# Main.net
KiCad netlist of a schematic drawn in Altium Designer
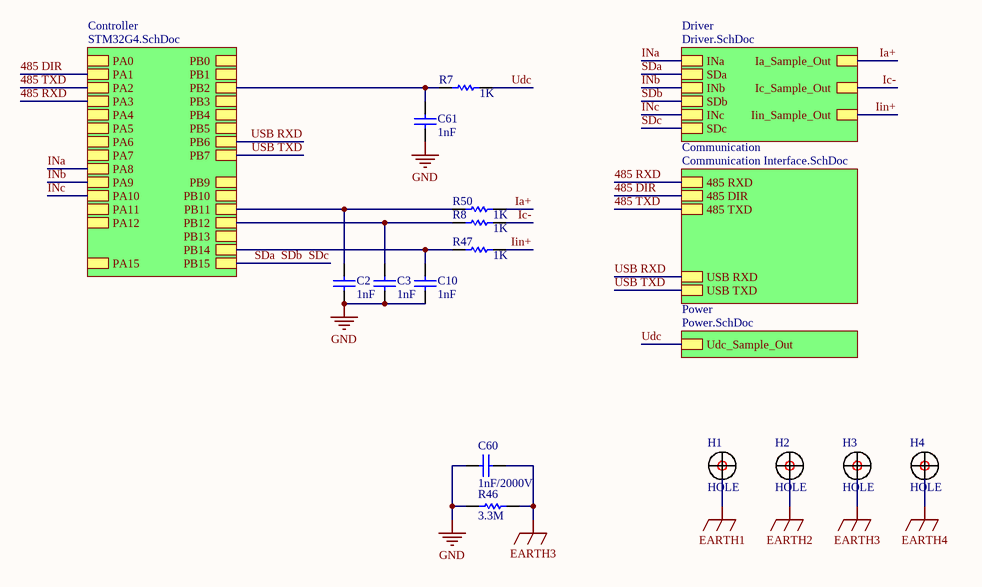
[diagram p0: Main.SchDoc]

(export (version "E")
  (design (tool "Eeschema 10.0.6"))
  (components
    (comp (ref "C2") (value "1nF") (footprint "C0402") (libsource (lib "Cap") (part "Cap")))
    (comp (ref "C3") (value "1nF") (footprint "C0402") (libsource (lib "Cap") (part "Cap")))
    (comp (ref "C10") (value "1nF") (footprint "C0402") (libsource (lib "Cap") (part "Cap")))
    (comp (ref "C60") (value "1nF/2000V") (footprint "C1206") (libsource (lib "Cap") (part "Cap")))
    (comp (ref "C61") (value "1nF") (footprint "C0402") (libsource (lib "Cap") (part "Cap")))
    (comp (ref "H1") (value "HOLE") (footprint "定位孔 Φ3 1") (libsource (lib "mylib") (part "HOLE")))
    (comp (ref "H2") (value "HOLE") (footprint "定位孔 Φ3 1") (libsource (lib "mylib") (part "HOLE")))
    (comp (ref "H3") (value "HOLE") (footprint "定位孔 Φ3 1") (libsource (lib "mylib") (part "HOLE")))
    (comp (ref "H4") (value "HOLE") (footprint "定位孔 Φ3 1") (libsource (lib "mylib") (part "HOLE")))
    (comp (ref "R7") (value "1K") (footprint "R0402") (libsource (lib "Res") (part "RES")))
    (comp (ref "R8") (value "1K") (footprint "R0402") (libsource (lib "Res") (part "RES")))
    (comp (ref "R46") (value "3.3M") (footprint "R1206") (libsource (lib "Res") (part "RES")))
    (comp (ref "R47") (value "1K") (footprint "R0402") (libsource (lib "Res") (part "RES")))
    (comp (ref "R50") (value "1K") (footprint "R0402") (libsource (lib "Res") (part "RES")))
  )
  (nets
    (net (code "7") (name "/Ia+") (class "Default")
      (node (ref "R50") (pin "1") (pinfunction "1_1") (pintype "passive"))
    )
    (net (code "8") (name "/Ic-") (class "Default")
      (node (ref "R8") (pin "1") (pinfunction "1_1") (pintype "passive"))
    )
    (net (code "9") (name "/Iin+") (class "Default")
      (node (ref "R47") (pin "1") (pinfunction "1_1") (pintype "passive"))
    )
    (net (code "20") (name "/PB2") (class "Default")
      (node (ref "C61") (pin "1") (pinfunction "1_1") (pintype "passive"))
      (node (ref "R7") (pin "2") (pinfunction "2_2") (pintype "passive"))
    )
    (net (code "26") (name "/PB11") (class "Default")
      (node (ref "C2") (pin "1") (pinfunction "1_1") (pintype "passive"))
      (node (ref "R50") (pin "2") (pinfunction "2_2") (pintype "passive"))
    )
    (net (code "27") (name "/PB12") (class "Default")
      (node (ref "C3") (pin "1") (pinfunction "1_1") (pintype "passive"))
      (node (ref "R8") (pin "2") (pinfunction "2_2") (pintype "passive"))
    )
    (net (code "29") (name "/PB14") (class "Default")
      (node (ref "C10") (pin "1") (pinfunction "1_1") (pintype "passive"))
      (node (ref "R47") (pin "2") (pinfunction "2_2") (pintype "passive"))
    )
    (net (code "33") (name "/Udc") (class "Default")
      (node (ref "R7") (pin "1") (pinfunction "1_1") (pintype "passive"))
    )
    (net (code "34") (name "EARTH1") (class "Default") (node (ref "H1") (pin "1") (pintype "passive")))
    (net (code "35") (name "EARTH2") (class "Default") (node (ref "H2") (pin "1") (pintype "passive")))
    (net (code "36") (name "EARTH3") (class "Default")
      (node (ref "C60") (pin "2") (pinfunction "2_2") (pintype "passive"))
      (node (ref "H3") (pin "1") (pintype "passive"))
      (node (ref "R46") (pin "1") (pinfunction "1_1") (pintype "passive"))
    )
    (net (code "37") (name "EARTH4") (class "Default") (node (ref "H4") (pin "1") (pintype "passive")))
    (net (code "38") (name "GND") (class "Default")
      (node (ref "C10") (pin "2") (pinfunction "2_2") (pintype "passive"))
      (node (ref "C2") (pin "2") (pinfunction "2_2") (pintype "passive"))
      (node (ref "C3") (pin "2") (pinfunction "2_2") (pintype "passive"))
      (node (ref "C60") (pin "1") (pinfunction "1_1") (pintype "passive"))
      (node (ref "C61") (pin "2") (pinfunction "2_2") (pintype "passive"))
      (node (ref "R46") (pin "2") (pinfunction "2_2") (pintype "passive"))
    )
  )
)
